# MCU.net
KiCad netlist of a schematic drawn in Altium Designer
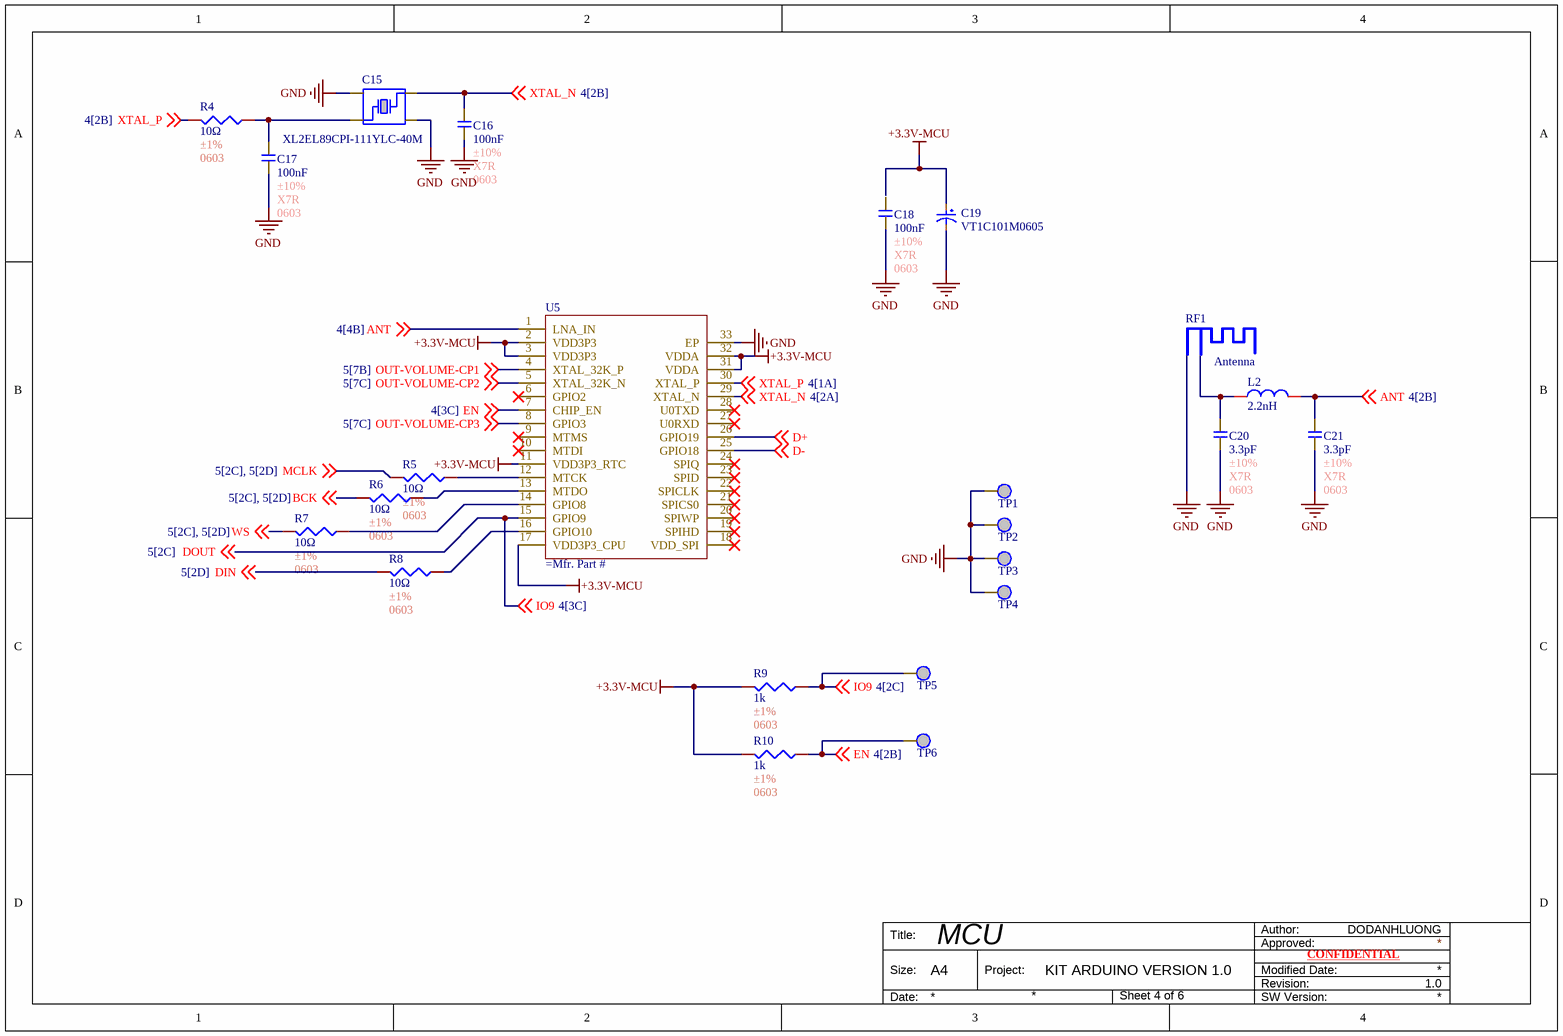
[diagram p0: MCU.SchDoc]

(export (version "E")
  (design (tool "Eeschema 10.0.6"))
  (components
    (comp (ref "C15")
      (value "XL2EL89CPI-111YLC-40M")
      (footprint "XL2EL89CPI-111YLC-40M")
      (description "Crystal Oscillator 15pF SMD3225-4P Crystals RoHS")
      (fields (field (name "MANUFACTURER") "YXC Crystal Oscillators") (field (name "LCSC PART #") "C5444549"))
      (libsource (lib "Oscillator") (part "XL2EL89CPI-111YLC-40M"))
    )
    (comp (ref "C16")
      (value "100nF")
      (footprint "C0603")
      (description "50V 100nF X7R ±10% 0603 Multilayer Ceramic Capacitors MLCC - SMD/SMT ROHS")
      (fields
        (field (name "MANUFACTURER") "YAGEO")
        (field (name "MFR. PART #") "CC0603KRX7R9BB104")
        (field (name "TOLERANCE") "±10%")
        (field (name "TEMPERATURE COEFFICIENT") "X7R")
        (field (name "PACKAGE") "0603")
      )
      (libsource (lib "DSP_VERSION_1.0") (part "C0603_100nF_±10%_X7R"))
    )
    (comp (ref "C17")
      (value "100nF")
      (footprint "C0603")
      (description "50V 100nF X7R ±10% 0603 Multilayer Ceramic Capacitors MLCC - SMD/SMT ROHS")
      (fields
        (field (name "MANUFACTURER") "YAGEO")
        (field (name "MFR. PART #") "CC0603KRX7R9BB104")
        (field (name "TOLERANCE") "±10%")
        (field (name "TEMPERATURE COEFFICIENT") "X7R")
        (field (name "PACKAGE") "0603")
      )
      (libsource (lib "DSP_VERSION_1.0") (part "C0603_100nF_±10%_X7R"))
    )
    (comp (ref "C18")
      (value "100nF")
      (footprint "C0603")
      (description "50V 100nF X7R ±10% 0603 Multilayer Ceramic Capacitors MLCC - SMD/SMT ROHS")
      (fields
        (field (name "MANUFACTURER") "YAGEO")
        (field (name "MFR. PART #") "CC0603KRX7R9BB104")
        (field (name "TOLERANCE") "±10%")
        (field (name "TEMPERATURE COEFFICIENT") "X7R")
        (field (name "PACKAGE") "0603")
      )
      (libsource (lib "DSP_VERSION_1.0") (part "C0603_100nF_±10%_X7R"))
    )
    (comp (ref "C19")
      (value "VT1C101M0605")
      (footprint "C_100uF_16V_Aluminum")
      (description "100uF 16V ±20% 63mA@120Hz SMD,D6.3xL5.4mm Aluminum Electrolytic Capacitors RoHS")
      (fields (field (name "MANUFACTURER") "ROQANG") (field (name "LCSC PART #") "C90273"))
      (libsource (lib "Capital") (part "C_100uF_16V_aluminum"))
    )
    (comp (ref "C20")
      (value "3.3pF")
      (footprint "C0603")
      (description "50V 100nF X7R ±10% 0603 Multilayer Ceramic Capacitors MLCC - SMD/SMT ROHS")
      (fields
        (field (name "MANUFACTURER") "YAGEO")
        (field (name "MFR. PART #") "CC0603KRX7R9BB104")
        (field (name "TOLERANCE") "±10%")
        (field (name "TEMPERATURE COEFFICIENT") "X7R")
        (field (name "PACKAGE") "0603")
      )
      (libsource (lib "DSP_VERSION_1.0") (part "C0603_100nF_±10%_X7R"))
    )
    (comp (ref "C21")
      (value "3.3pF")
      (footprint "C0603")
      (description "50V 100nF X7R ±10% 0603 Multilayer Ceramic Capacitors MLCC - SMD/SMT ROHS")
      (fields
        (field (name "MANUFACTURER") "YAGEO")
        (field (name "MFR. PART #") "CC0603KRX7R9BB104")
        (field (name "TOLERANCE") "±10%")
        (field (name "TEMPERATURE COEFFICIENT") "X7R")
        (field (name "PACKAGE") "0603")
      )
      (libsource (lib "DSP_VERSION_1.0") (part "C0603_100nF_±10%_X7R"))
    )
    (comp (ref "L2")
      (value "2.2nH")
      (footprint "CD43")
      (description "1.15A 10uH Unshielded Inductor ±20% SMD,4x4.5mm Power Inductors ROHS")
      (fields (field (name "MANUFACTURER") "ZE") (field (name "MFR. PART #") "CD43-100M"))
      (libsource (lib "Inductor") (part "CD4-10UH"))
    )
    (comp (ref "R4")
      (value "10Ω")
      (footprint "R0603")
      (description "62.5mW Thick Film Resistor 50V ±1% ±200ppm/℃ 10Ω 0402 Chip Resistor - Surface Mount ROHS")
      (fields
        (field (name "MANUFACTURER") "YAGEO")
        (field (name "MFR. PART #") "RC0402FR-0710RL")
        (field (name "TOLERANCE") "±1%")
        (field (name "PACKAGE") "0603")
      )
      (libsource (lib "Resistor") (part "R0603_10Ω_±1%"))
    )
    (comp (ref "R5")
      (value "10Ω")
      (footprint "R0603")
      (description "62.5mW Thick Film Resistor 50V ±1% ±200ppm/℃ 10Ω 0402 Chip Resistor - Surface Mount ROHS")
      (fields
        (field (name "MANUFACTURER") "YAGEO")
        (field (name "MFR. PART #") "RC0402FR-0710RL")
        (field (name "TOLERANCE") "±1%")
        (field (name "PACKAGE") "0603")
      )
      (libsource (lib "Resistor") (part "R0603_10Ω_±1%"))
    )
    (comp (ref "R6")
      (value "10Ω")
      (footprint "R0603")
      (description "62.5mW Thick Film Resistor 50V ±1% ±200ppm/℃ 10Ω 0402 Chip Resistor - Surface Mount ROHS")
      (fields
        (field (name "MANUFACTURER") "YAGEO")
        (field (name "MFR. PART #") "RC0402FR-0710RL")
        (field (name "TOLERANCE") "±1%")
        (field (name "PACKAGE") "0603")
      )
      (libsource (lib "Resistor") (part "R0603_10Ω_±1%"))
    )
    (comp (ref "R7")
      (value "10Ω")
      (footprint "R0603")
      (description "62.5mW Thick Film Resistor 50V ±1% ±200ppm/℃ 10Ω 0402 Chip Resistor - Surface Mount ROHS")
      (fields
        (field (name "MANUFACTURER") "YAGEO")
        (field (name "MFR. PART #") "RC0402FR-0710RL")
        (field (name "TOLERANCE") "±1%")
        (field (name "PACKAGE") "0603")
      )
      (libsource (lib "Resistor") (part "R0603_10Ω_±1%"))
    )
    (comp (ref "R8")
      (value "10Ω")
      (footprint "R0603")
      (description "62.5mW Thick Film Resistor 50V ±1% ±200ppm/℃ 10Ω 0402 Chip Resistor - Surface Mount ROHS")
      (fields
        (field (name "MANUFACTURER") "YAGEO")
        (field (name "MFR. PART #") "RC0402FR-0710RL")
        (field (name "TOLERANCE") "±1%")
        (field (name "PACKAGE") "0603")
      )
      (libsource (lib "Resistor") (part "R0603_10Ω_±1%"))
    )
    (comp (ref "R9")
      (value "1k")
      (footprint "R0603")
      (description "62.5mW Thick Film Resistor 50V ±1% ±200ppm/℃ 10Ω 0402 Chip Resistor - Surface Mount ROHS")
      (fields
        (field (name "MANUFACTURER") "YAGEO")
        (field (name "MFR. PART #") "RC0402FR-0710RL")
        (field (name "TOLERANCE") "±1%")
        (field (name "PACKAGE") "0603")
      )
      (libsource (lib "Resistor") (part "R0603_10Ω_±1%"))
    )
    (comp (ref "R10")
      (value "1k")
      (footprint "R0603")
      (description "62.5mW Thick Film Resistor 50V ±1% ±200ppm/℃ 10Ω 0402 Chip Resistor - Surface Mount ROHS")
      (fields
        (field (name "MANUFACTURER") "YAGEO")
        (field (name "MFR. PART #") "RC0402FR-0710RL")
        (field (name "TOLERANCE") "±1%")
        (field (name "PACKAGE") "0603")
      )
      (libsource (lib "Resistor") (part "R0603_10Ω_±1%"))
    )
    (comp (ref "RF1")
      (value "Antenna")
      (footprint "2.4GHZ-50OHMS_v1.1")
      (libsource (lib "Antenna") (part "Antenna"))
    )
    (comp (ref "TP1") (value "TP") (footprint "TP") (libsource (lib "Other") (part "TP")))
    (comp (ref "TP2") (value "TP") (footprint "TP") (libsource (lib "Other") (part "TP")))
    (comp (ref "TP3") (value "TP") (footprint "TP") (libsource (lib "Other") (part "TP")))
    (comp (ref "TP4") (value "TP") (footprint "TP") (libsource (lib "Other") (part "TP")))
    (comp (ref "TP5") (value "TP") (footprint "TP") (libsource (lib "Other") (part "TP")))
    (comp (ref "TP6") (value "TP") (footprint "TP") (libsource (lib "Other") (part "TP")))
    (comp (ref "U5")
      (value "~")
      (footprint "ESP32-C3")
      (description "Others 160MHz QFN-32-EP(5x5) RF Transceiver Modules and Modems RoHS")
      (fields (field (name "MANUFACTURER") "ESPRESSIF") (field (name "LCSC PART #") "C2838500"))
      (libsource (lib "MCU") (part "ESP32-C3"))
    )
  )
  (nets
    (net (code "1") (name "+3.3V-MCU") (class "Default")
      (node (ref "C19") (pin "1") (pinfunction "1_1") (pintype "passive"))
      (node (ref "R10") (pin "2") (pinfunction "2_2") (pintype "passive"))
      (node (ref "R9") (pin "2") (pinfunction "2_2") (pintype "passive"))
      (node (ref "U5") (pin "11") (pinfunction "VDD3P3_RTC_11") (pintype "passive"))
      (node (ref "U5") (pin "17") (pinfunction "VDD3P3_CPU_17") (pintype "passive"))
      (node (ref "U5") (pin "2") (pinfunction "VDD3P3_2") (pintype "passive"))
      (node (ref "U5") (pin "3") (pinfunction "VDD3P3_3") (pintype "passive"))
      (node (ref "U5") (pin "31") (pinfunction "VDDA_31") (pintype "passive"))
      (node (ref "U5") (pin "32") (pinfunction "VDDA_32") (pintype "passive"))
    )
    (net (code "2") (name "ANT") (class "Default")
      (node (ref "C21") (pin "2") (pinfunction "2_2") (pintype "passive"))
      (node (ref "L2") (pin "2") (pinfunction "2_2") (pintype "passive"))
      (node (ref "U5") (pin "1") (pinfunction "LNA_IN_1") (pintype "passive"))
    )
    (net (code "3") (name "BCK") (class "Default")
      (node (ref "R6") (pin "2") (pinfunction "2_2") (pintype "passive"))
    )
    (net (code "4") (name "D+") (class "Default")
      (node (ref "U5") (pin "26") (pinfunction "GPIO19_26") (pintype "passive"))
    )
    (net (code "5") (name "D-") (class "Default")
      (node (ref "U5") (pin "25") (pinfunction "GPIO18_25") (pintype "passive"))
    )
    (net (code "6") (name "DIN") (class "Default")
      (node (ref "R8") (pin "2") (pinfunction "2_2") (pintype "passive"))
    )
    (net (code "7") (name "DOUT") (class "Default")
      (node (ref "R9") (pin "1") (pinfunction "1_1") (pintype "passive"))
      (node (ref "TP5") (pin "1") (pinfunction "1_1") (pintype "passive"))
      (node (ref "U5") (pin "15") (pinfunction "GPIO9_15") (pintype "passive"))
    )
    (net (code "8") (name "EN") (class "Default")
      (node (ref "R10") (pin "1") (pinfunction "1_1") (pintype "passive"))
      (node (ref "TP6") (pin "1") (pinfunction "1_1") (pintype "passive"))
      (node (ref "U5") (pin "7") (pinfunction "CHIP_EN_7") (pintype "passive"))
    )
    (net (code "9") (name "GND") (class "Default")
      (node (ref "C15") (pin "2") (pinfunction "2_2") (pintype "passive"))
      (node (ref "C15") (pin "4") (pinfunction "4_4") (pintype "passive"))
      (node (ref "C16") (pin "1") (pinfunction "1_1") (pintype "passive"))
      (node (ref "C17") (pin "1") (pinfunction "1_1") (pintype "passive"))
      (node (ref "C18") (pin "1") (pinfunction "1_1") (pintype "passive"))
      (node (ref "C19") (pin "2") (pinfunction "2_2") (pintype "passive"))
      (node (ref "C20") (pin "1") (pinfunction "1_1") (pintype "passive"))
      (node (ref "C21") (pin "1") (pinfunction "1_1") (pintype "passive"))
      (node (ref "RF1") (pin "2") (pinfunction "2_2") (pintype "passive"))
      (node (ref "TP1") (pin "1") (pinfunction "1_1") (pintype "passive"))
      (node (ref "TP2") (pin "1") (pinfunction "1_1") (pintype "passive"))
      (node (ref "TP3") (pin "1") (pinfunction "1_1") (pintype "passive"))
      (node (ref "TP4") (pin "1") (pinfunction "1_1") (pintype "passive"))
      (node (ref "U5") (pin "33") (pinfunction "EP_33") (pintype "passive"))
    )
    (net (code "10") (name "MCLK") (class "Default")
      (node (ref "R5") (pin "2") (pinfunction "2_2") (pintype "passive"))
    )
    (net (code "11") (name "Net-(C15-Pad1)") (class "Default")
      (node (ref "C15") (pin "1") (pinfunction "1_1") (pintype "passive"))
      (node (ref "C17") (pin "2") (pinfunction "2_2") (pintype "passive"))
      (node (ref "R4") (pin "1") (pinfunction "1_1") (pintype "passive"))
    )
    (net (code "12") (name "Net-(C20-Pad2)") (class "Default")
      (node (ref "C20") (pin "2") (pinfunction "2_2") (pintype "passive"))
      (node (ref "L2") (pin "1") (pinfunction "1_1") (pintype "passive"))
      (node (ref "RF1") (pin "1") (pinfunction "1_1") (pintype "passive"))
    )
    (net (code "13") (name "Net-(U5-GPIO8)") (class "Default")
      (node (ref "R7") (pin "1") (pinfunction "1_1") (pintype "passive"))
      (node (ref "U5") (pin "14") (pinfunction "GPIO8_14") (pintype "passive"))
    )
    (net (code "14") (name "Net-(U5-GPIO10)") (class "Default")
      (node (ref "R8") (pin "1") (pinfunction "1_1") (pintype "passive"))
      (node (ref "U5") (pin "16") (pinfunction "GPIO10_16") (pintype "passive"))
    )
    (net (code "15") (name "Net-(U5-MTCK)") (class "Default")
      (node (ref "R5") (pin "1") (pinfunction "1_1") (pintype "passive"))
      (node (ref "U5") (pin "12") (pinfunction "MTCK_12") (pintype "passive"))
    )
    (net (code "16") (name "Net-(U5-MTDO)") (class "Default")
      (node (ref "R6") (pin "1") (pinfunction "1_1") (pintype "passive"))
      (node (ref "U5") (pin "13") (pinfunction "MTDO_13") (pintype "passive"))
    )
    (net (code "17") (name "OUT-VOLUME-CP1") (class "Default")
      (node (ref "U5") (pin "4") (pinfunction "XTAL_32K_P_4") (pintype "passive"))
    )
    (net (code "18") (name "OUT-VOLUME-CP2") (class "Default")
      (node (ref "U5") (pin "5") (pinfunction "XTAL_32K_N_5") (pintype "passive"))
    )
    (net (code "19") (name "OUT-VOLUME-CP3") (class "Default")
      (node (ref "U5") (pin "8") (pinfunction "GPIO3_8") (pintype "passive"))
    )
    (net (code "20") (name "WS") (class "Default")
      (node (ref "R7") (pin "2") (pinfunction "2_2") (pintype "passive"))
    )
    (net (code "21") (name "XTAL_N") (class "Default")
      (node (ref "C15") (pin "3") (pinfunction "3_3") (pintype "passive"))
      (node (ref "C16") (pin "2") (pinfunction "2_2") (pintype "passive"))
      (node (ref "U5") (pin "29") (pinfunction "XTAL_N_29") (pintype "passive"))
    )
    (net (code "22") (name "XTAL_P") (class "Default")
      (node (ref "R4") (pin "2") (pinfunction "2_2") (pintype "passive"))
      (node (ref "U5") (pin "30") (pinfunction "XTAL_P_30") (pintype "passive"))
    )
    (net (code "23") (name "unconnected-(C18-Pad2)") (class "Default")
      (node (ref "C18") (pin "2") (pinfunction "2_2") (pintype "passive"))
    )
    (net (code "24") (name "unconnected-(U5-GPIO2-Pad6)") (class "Default")
      (node (ref "U5") (pin "6") (pinfunction "GPIO2_6") (pintype "passive+no_connect"))
    )
    (net (code "25") (name "unconnected-(U5-MTDI-Pad10)") (class "Default")
      (node (ref "U5") (pin "10") (pinfunction "MTDI_10") (pintype "passive+no_connect"))
    )
    (net (code "26") (name "unconnected-(U5-MTMS-Pad9)") (class "Default")
      (node (ref "U5") (pin "9") (pinfunction "MTMS_9") (pintype "passive+no_connect"))
    )
    (net (code "27") (name "unconnected-(U5-SPICLK-Pad22)") (class "Default")
      (node (ref "U5") (pin "22") (pinfunction "SPICLK_22") (pintype "passive+no_connect"))
    )
    (net (code "28") (name "unconnected-(U5-SPICS0-Pad21)") (class "Default")
      (node (ref "U5") (pin "21") (pinfunction "SPICS0_21") (pintype "passive+no_connect"))
    )
    (net (code "29") (name "unconnected-(U5-SPID-Pad23)") (class "Default")
      (node (ref "U5") (pin "23") (pinfunction "SPID_23") (pintype "passive+no_connect"))
    )
    (net (code "30") (name "unconnected-(U5-SPIHD-Pad19)") (class "Default")
      (node (ref "U5") (pin "19") (pinfunction "SPIHD_19") (pintype "passive+no_connect"))
    )
    (net (code "31") (name "unconnected-(U5-SPIQ-Pad24)") (class "Default")
      (node (ref "U5") (pin "24") (pinfunction "SPIQ_24") (pintype "passive+no_connect"))
    )
    (net (code "32") (name "unconnected-(U5-SPIWP-Pad20)") (class "Default")
      (node (ref "U5") (pin "20") (pinfunction "SPIWP_20") (pintype "passive+no_connect"))
    )
    (net (code "33") (name "unconnected-(U5-U0RXD-Pad27)") (class "Default")
      (node (ref "U5") (pin "27") (pinfunction "U0RXD_27") (pintype "passive+no_connect"))
    )
    (net (code "34") (name "unconnected-(U5-U0TXD-Pad28)") (class "Default")
      (node (ref "U5") (pin "28") (pinfunction "U0TXD_28") (pintype "passive+no_connect"))
    )
    (net (code "35") (name "unconnected-(U5-VDD_SPI-Pad18)") (class "Default")
      (node (ref "U5") (pin "18") (pinfunction "VDD_SPI_18") (pintype "passive+no_connect"))
    )
  )
)
